# OS-MPS_Preamp_V1.net
KiCad netlist of a schematic drawn in EAGLE
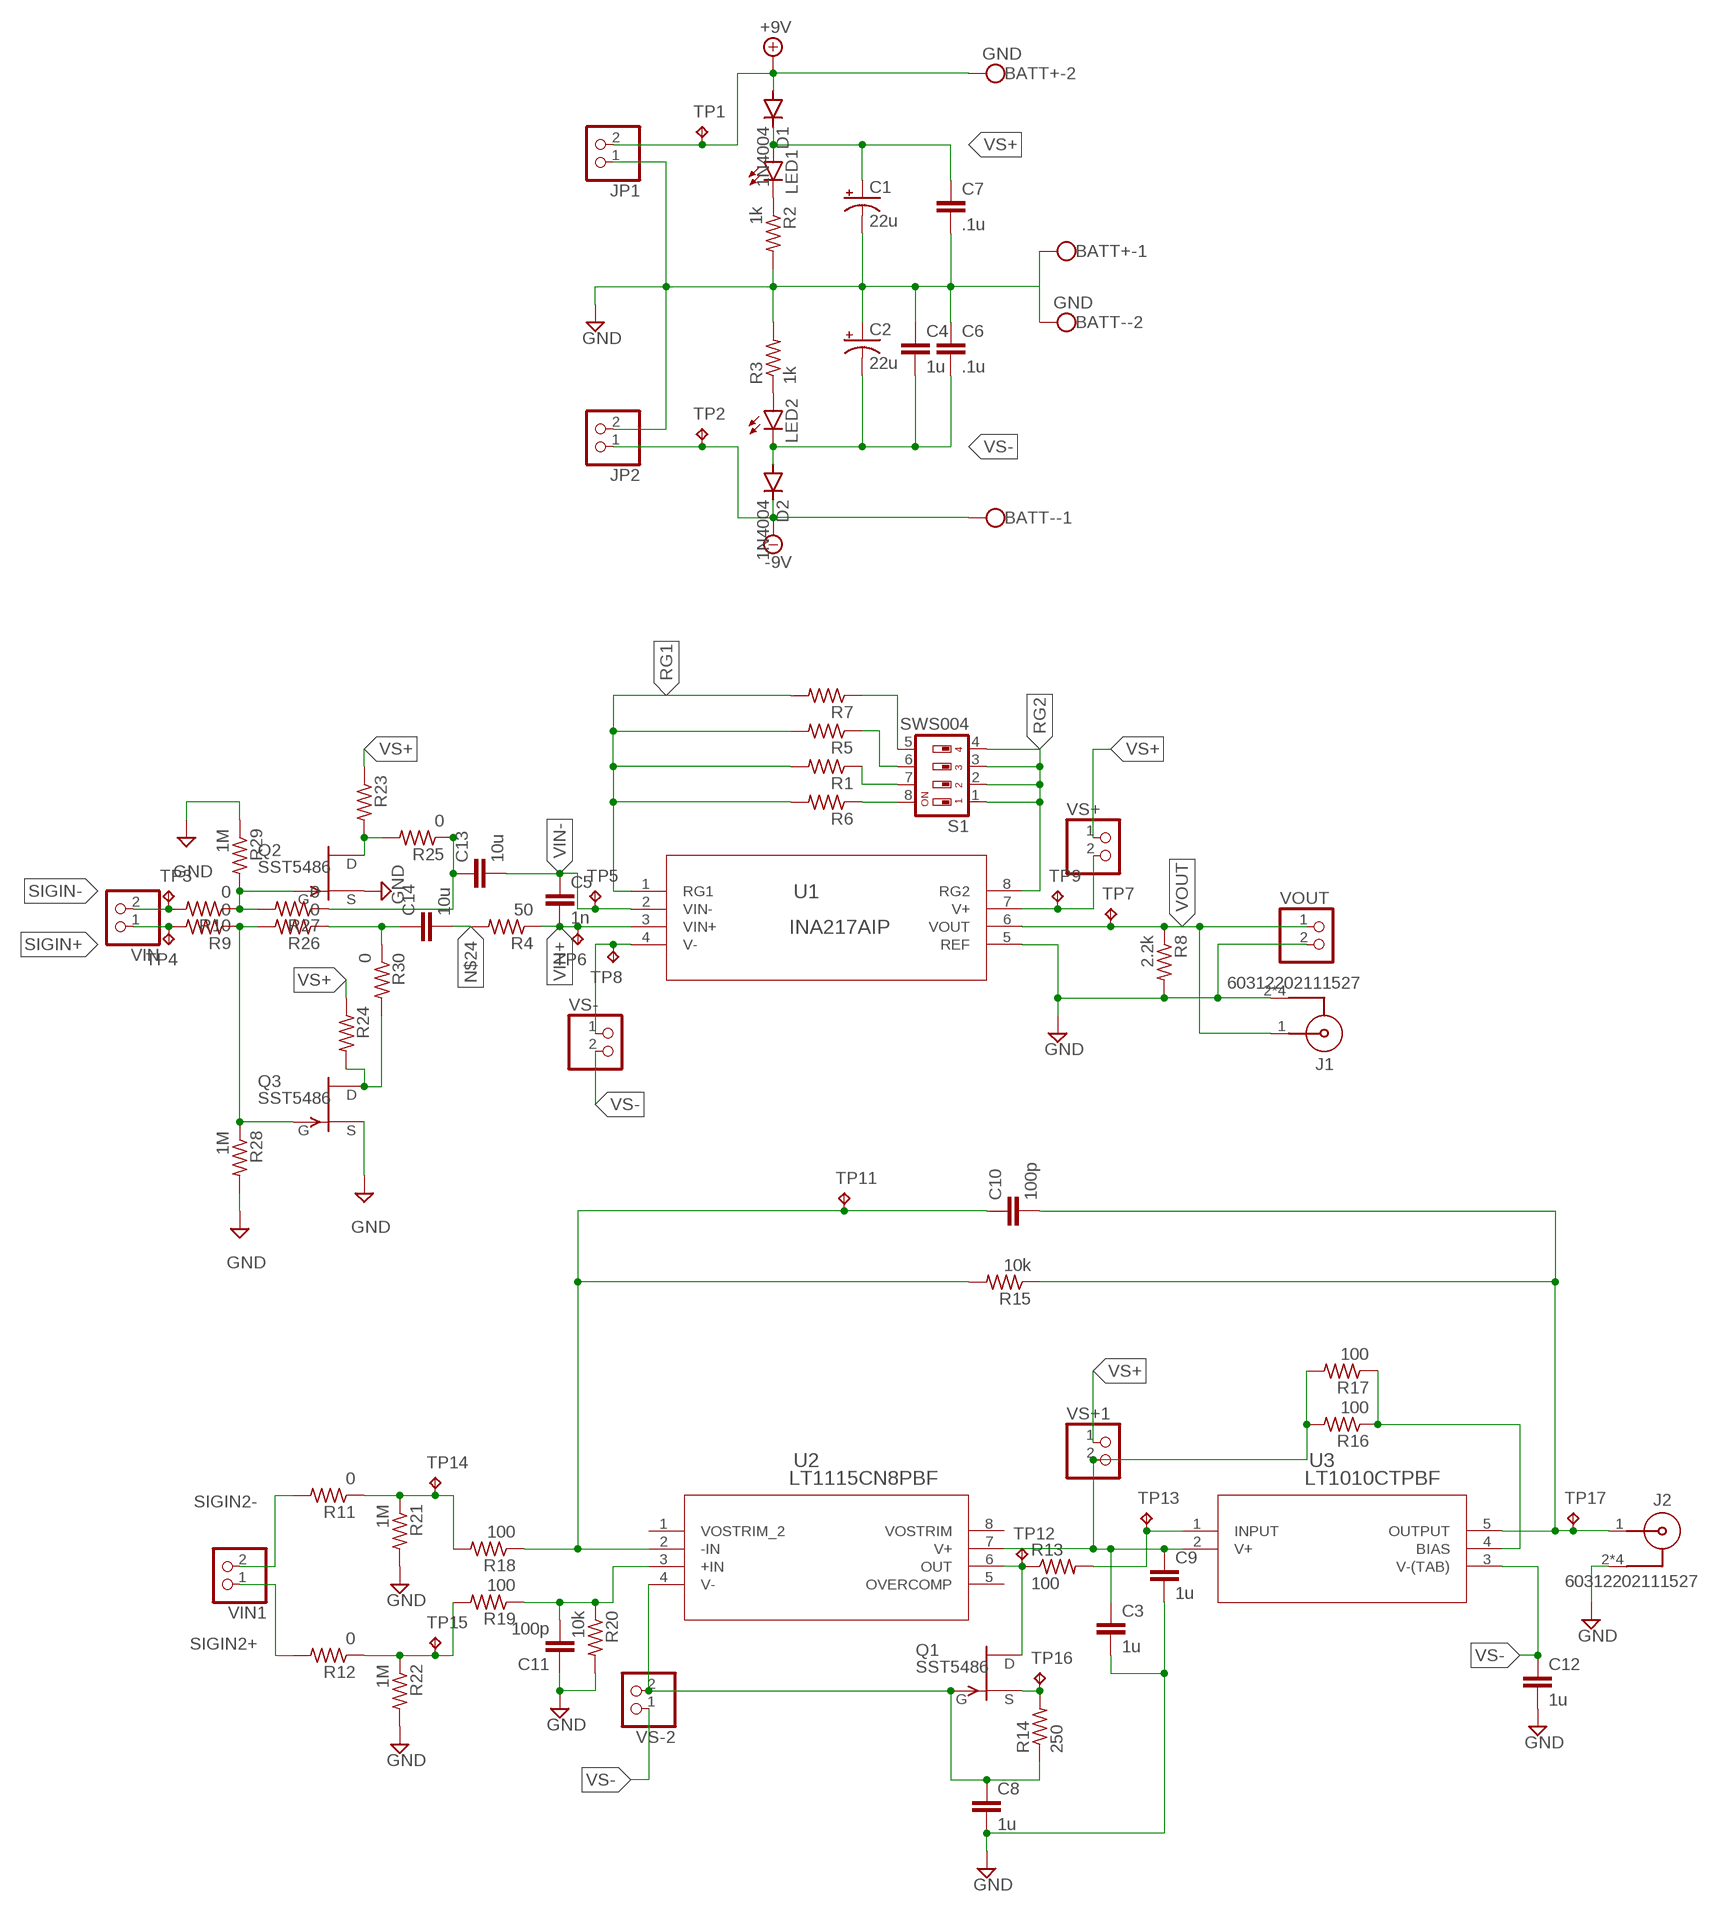
[diagram p0: schematic, sheet 1]

(export (version "E")
  (design (tool "Eeschema 10.0.6"))
  (components
    (comp (ref "BATT+")
      (value "GND")
      (footprint "eagle-import:W237-102")
      (fields (field (name "MPN") "237-102"))
      (libsource (lib "eagle-import") (part "W237-102"))
    )
    (comp (ref "BATT-")
      (value "GND")
      (footprint "eagle-import:W237-102")
      (fields (field (name "MPN") "237-102"))
      (libsource (lib "eagle-import") (part "W237-102"))
    )
    (comp (ref "C1")
      (value "22u")
      (footprint "eagle-import:TT2D6")
      (libsource (lib "eagle-import") (part "CPOL-USTT2D6"))
    )
    (comp (ref "C2")
      (value "22u")
      (footprint "eagle-import:TT2D6")
      (libsource (lib "eagle-import") (part "CPOL-USTT2D6"))
    )
    (comp (ref "C3")
      (value "1u")
      (footprint "eagle-import:C1206")
      (libsource (lib "eagle-import") (part "C-EUC1206"))
    )
    (comp (ref "C4")
      (value "1u")
      (footprint "eagle-import:C1206")
      (libsource (lib "eagle-import") (part "C-EUC1206"))
    )
    (comp (ref "C5")
      (value "1n")
      (footprint "eagle-import:C1206")
      (libsource (lib "eagle-import") (part "C-EUC1206"))
    )
    (comp (ref "C6")
      (value ".1u")
      (footprint "eagle-import:C1206")
      (libsource (lib "eagle-import") (part "C-EUC1206"))
    )
    (comp (ref "C7")
      (value ".1u")
      (footprint "eagle-import:C1206")
      (libsource (lib "eagle-import") (part "C-EUC1206"))
    )
    (comp (ref "C8")
      (value "1u")
      (footprint "eagle-import:C1206")
      (libsource (lib "eagle-import") (part "C-EUC1206"))
    )
    (comp (ref "C9")
      (value "1u")
      (footprint "eagle-import:C1206")
      (libsource (lib "eagle-import") (part "C-EUC1206"))
    )
    (comp (ref "C10")
      (value "100p")
      (footprint "eagle-import:C1206")
      (libsource (lib "eagle-import") (part "C-EUC1206"))
    )
    (comp (ref "C11")
      (value "100p")
      (footprint "eagle-import:C1206")
      (libsource (lib "eagle-import") (part "C-EUC1206"))
    )
    (comp (ref "C12")
      (value "1u")
      (footprint "eagle-import:C1206")
      (libsource (lib "eagle-import") (part "C-EUC1206"))
    )
    (comp (ref "C13")
      (value "10u")
      (footprint "eagle-import:C1206")
      (libsource (lib "eagle-import") (part "C-EUC1206"))
    )
    (comp (ref "C14")
      (value "10u")
      (footprint "eagle-import:C1206")
      (libsource (lib "eagle-import") (part "C-EUC1206"))
    )
    (comp (ref "D1")
      (value "1N4004")
      (footprint "eagle-import:DO41-10")
      (libsource (lib "eagle-import") (part "1N4004"))
    )
    (comp (ref "D2")
      (value "1N4004")
      (footprint "eagle-import:DO41-10")
      (libsource (lib "eagle-import") (part "1N4004"))
    )
    (comp (ref "J1")
      (value "60312202111527")
      (footprint "eagle-import:60312202111527")
      (libsource (lib "eagle-import") (part "60312202111527"))
    )
    (comp (ref "J2")
      (value "60312202111527")
      (footprint "eagle-import:60312202111527")
      (libsource (lib "eagle-import") (part "60312202111527"))
    )
    (comp (ref "JP1")
      (value "PINHD-1X2")
      (footprint "eagle-import:1X02")
      (libsource (lib "eagle-import") (part "PINHD-1X2"))
    )
    (comp (ref "JP2")
      (value "PINHD-1X2")
      (footprint "eagle-import:1X02")
      (libsource (lib "eagle-import") (part "PINHD-1X2"))
    )
    (comp (ref "LED1")
      (value "LEDSML0805")
      (footprint "eagle-import:SML0805")
      (libsource (lib "eagle-import") (part "LEDSML0805"))
    )
    (comp (ref "LED2")
      (value "LEDSML0805")
      (footprint "eagle-import:SML0805")
      (libsource (lib "eagle-import") (part "LEDSML0805"))
    )
    (comp (ref "Q1")
      (value "SST5486")
      (footprint "eagle-import:SOT23")
      (libsource (lib "eagle-import") (part "?548SST6"))
    )
    (comp (ref "Q2")
      (value "SST5486")
      (footprint "eagle-import:SOT23")
      (libsource (lib "eagle-import") (part "?548SST6"))
    )
    (comp (ref "Q3")
      (value "SST5486")
      (footprint "eagle-import:SOT23")
      (libsource (lib "eagle-import") (part "?548SST6"))
    )
    (comp (ref "R1")
      (value "R-US_R0805")
      (footprint "eagle-import:R0805")
      (libsource (lib "eagle-import") (part "R-US_R0805"))
    )
    (comp (ref "R2")
      (value "1k")
      (footprint "eagle-import:R0805")
      (libsource (lib "eagle-import") (part "R-US_R0805"))
    )
    (comp (ref "R3")
      (value "1k")
      (footprint "eagle-import:R0805")
      (libsource (lib "eagle-import") (part "R-US_R0805"))
    )
    (comp (ref "R4")
      (value "50")
      (footprint "eagle-import:R0805")
      (libsource (lib "eagle-import") (part "R-US_R0805"))
    )
    (comp (ref "R5")
      (value "R-US_R0805")
      (footprint "eagle-import:R0805")
      (libsource (lib "eagle-import") (part "R-US_R0805"))
    )
    (comp (ref "R6")
      (value "R-US_R0805")
      (footprint "eagle-import:R0805")
      (libsource (lib "eagle-import") (part "R-US_R0805"))
    )
    (comp (ref "R7")
      (value "R-US_R0805")
      (footprint "eagle-import:R0805")
      (libsource (lib "eagle-import") (part "R-US_R0805"))
    )
    (comp (ref "R8")
      (value "2.2k")
      (footprint "eagle-import:R0805")
      (libsource (lib "eagle-import") (part "R-US_R0805"))
    )
    (comp (ref "R9")
      (value "0")
      (footprint "eagle-import:R0805")
      (libsource (lib "eagle-import") (part "R-US_R0805"))
    )
    (comp (ref "R10")
      (value "0")
      (footprint "eagle-import:R0805")
      (libsource (lib "eagle-import") (part "R-US_R0805"))
    )
    (comp (ref "R11")
      (value "0")
      (footprint "eagle-import:R0805")
      (libsource (lib "eagle-import") (part "R-US_R0805"))
    )
    (comp (ref "R12")
      (value "0")
      (footprint "eagle-import:R0805")
      (libsource (lib "eagle-import") (part "R-US_R0805"))
    )
    (comp (ref "R13")
      (value "100")
      (footprint "eagle-import:R0805")
      (libsource (lib "eagle-import") (part "R-US_R0805"))
    )
    (comp (ref "R14")
      (value "250")
      (footprint "eagle-import:R0805")
      (libsource (lib "eagle-import") (part "R-US_R0805"))
    )
    (comp (ref "R15")
      (value "10k")
      (footprint "eagle-import:R0805")
      (libsource (lib "eagle-import") (part "R-US_R0805"))
    )
    (comp (ref "R16")
      (value "100")
      (footprint "eagle-import:R0805")
      (libsource (lib "eagle-import") (part "R-US_R0805"))
    )
    (comp (ref "R17")
      (value "100")
      (footprint "eagle-import:R0805")
      (libsource (lib "eagle-import") (part "R-US_R0805"))
    )
    (comp (ref "R18")
      (value "100")
      (footprint "eagle-import:R0805")
      (libsource (lib "eagle-import") (part "R-US_R0805"))
    )
    (comp (ref "R19")
      (value "100")
      (footprint "eagle-import:R0805")
      (libsource (lib "eagle-import") (part "R-US_R0805"))
    )
    (comp (ref "R20")
      (value "10k")
      (footprint "eagle-import:R0805")
      (libsource (lib "eagle-import") (part "R-US_R0805"))
    )
    (comp (ref "R21")
      (value "1M")
      (footprint "eagle-import:R0805")
      (libsource (lib "eagle-import") (part "R-US_R0805"))
    )
    (comp (ref "R22")
      (value "1M")
      (footprint "eagle-import:R0805")
      (libsource (lib "eagle-import") (part "R-US_R0805"))
    )
    (comp (ref "R23")
      (value "R-US_R0805")
      (footprint "eagle-import:R0805")
      (libsource (lib "eagle-import") (part "R-US_R0805"))
    )
    (comp (ref "R24")
      (value "R-US_R0805")
      (footprint "eagle-import:R0805")
      (libsource (lib "eagle-import") (part "R-US_R0805"))
    )
    (comp (ref "R25")
      (value "0")
      (footprint "eagle-import:R0805")
      (libsource (lib "eagle-import") (part "R-US_R0805"))
    )
    (comp (ref "R26")
      (value "0")
      (footprint "eagle-import:R0805")
      (libsource (lib "eagle-import") (part "R-US_R0805"))
    )
    (comp (ref "R27")
      (value "0")
      (footprint "eagle-import:R0805")
      (libsource (lib "eagle-import") (part "R-US_R0805"))
    )
    (comp (ref "R28")
      (value "1M")
      (footprint "eagle-import:R0805")
      (libsource (lib "eagle-import") (part "R-US_R0805"))
    )
    (comp (ref "R29")
      (value "1M")
      (footprint "eagle-import:R0805")
      (libsource (lib "eagle-import") (part "R-US_R0805"))
    )
    (comp (ref "R30")
      (value "0")
      (footprint "eagle-import:R0805")
      (libsource (lib "eagle-import") (part "R-US_R0805"))
    )
    (comp (ref "S1")
      (value "SWS004")
      (footprint "eagle-import:SMS-004")
      (libsource (lib "eagle-import") (part "SWS004"))
    )
    (comp (ref "TP1")
      (value "TPB2,54")
      (footprint "eagle-import:B2,54")
      (libsource (lib "eagle-import") (part "TPB2,54"))
    )
    (comp (ref "TP2")
      (value "TPB2,54")
      (footprint "eagle-import:B2,54")
      (libsource (lib "eagle-import") (part "TPB2,54"))
    )
    (comp (ref "TP3")
      (value "TPTP20SQ")
      (footprint "eagle-import:TP20SQ")
      (libsource (lib "eagle-import") (part "TPTP20SQ"))
    )
    (comp (ref "TP4")
      (value "TPTP20SQ")
      (footprint "eagle-import:TP20SQ")
      (libsource (lib "eagle-import") (part "TPTP20SQ"))
    )
    (comp (ref "TP5")
      (value "TPTP20SQ")
      (footprint "eagle-import:TP20SQ")
      (libsource (lib "eagle-import") (part "TPTP20SQ"))
    )
    (comp (ref "TP6")
      (value "TPTP20SQ")
      (footprint "eagle-import:TP20SQ")
      (libsource (lib "eagle-import") (part "TPTP20SQ"))
    )
    (comp (ref "TP7")
      (value "TPTP20SQ")
      (footprint "eagle-import:TP20SQ")
      (libsource (lib "eagle-import") (part "TPTP20SQ"))
    )
    (comp (ref "TP8")
      (value "TPTP20SQ")
      (footprint "eagle-import:TP20SQ")
      (libsource (lib "eagle-import") (part "TPTP20SQ"))
    )
    (comp (ref "TP9")
      (value "TPTP20SQ")
      (footprint "eagle-import:TP20SQ")
      (libsource (lib "eagle-import") (part "TPTP20SQ"))
    )
    (comp (ref "TP11")
      (value "TPTP20SQ")
      (footprint "eagle-import:TP20SQ")
      (libsource (lib "eagle-import") (part "TPTP20SQ"))
    )
    (comp (ref "TP12")
      (value "TPTP20SQ")
      (footprint "eagle-import:TP20SQ")
      (libsource (lib "eagle-import") (part "TPTP20SQ"))
    )
    (comp (ref "TP13")
      (value "TPTP20SQ")
      (footprint "eagle-import:TP20SQ")
      (libsource (lib "eagle-import") (part "TPTP20SQ"))
    )
    (comp (ref "TP14")
      (value "TPTP20SQ")
      (footprint "eagle-import:TP20SQ")
      (libsource (lib "eagle-import") (part "TPTP20SQ"))
    )
    (comp (ref "TP15")
      (value "TPTP20SQ")
      (footprint "eagle-import:TP20SQ")
      (libsource (lib "eagle-import") (part "TPTP20SQ"))
    )
    (comp (ref "TP16")
      (value "TPTP20SQ")
      (footprint "eagle-import:TP20SQ")
      (libsource (lib "eagle-import") (part "TPTP20SQ"))
    )
    (comp (ref "TP17")
      (value "TPTP20SQ")
      (footprint "eagle-import:TP20SQ")
      (libsource (lib "eagle-import") (part "TPTP20SQ"))
    )
    (comp (ref "U1")
      (value "INA217AIP")
      (footprint "eagle-import:P8")
      (fields (field (name "GENERIC_PART_NUMBER") "INA217") (field (name "MANUFACTURER") "Texas Instruments"))
      (libsource (lib "eagle-import") (part "INA217AIP"))
    )
    (comp (ref "U2")
      (value "LT1115CN8PBF")
      (footprint "eagle-import:PDIP-8_N_LIT")
      (fields (field (name "MANUFACTURER_PART_NUMBER") "LT1115CN8#PBF"))
      (libsource (lib "eagle-import") (part "LT1115CN8PBF"))
    )
    (comp (ref "U3")
      (value "LT1010CTPBF")
      (footprint "eagle-import:TO220-5_T")
      (fields (field (name "MANUFACTURER_PART_NUMBER") "LT1010CT#PBF"))
      (libsource (lib "eagle-import") (part "LT1010CTPBF"))
    )
    (comp (ref "VIN")
      (value "PINHD-1X2")
      (footprint "eagle-import:1X02")
      (libsource (lib "eagle-import") (part "PINHD-1X2"))
    )
    (comp (ref "VIN1")
      (value "PINHD-1X2")
      (footprint "eagle-import:1X02")
      (libsource (lib "eagle-import") (part "PINHD-1X2"))
    )
    (comp (ref "VOUT")
      (value "PINHD-1X2")
      (footprint "eagle-import:1X02")
      (libsource (lib "eagle-import") (part "PINHD-1X2"))
    )
    (comp (ref "VS+")
      (value "PINHD-1X2")
      (footprint "eagle-import:1X02")
      (libsource (lib "eagle-import") (part "PINHD-1X2"))
    )
    (comp (ref "VS+1")
      (value "PINHD-1X2")
      (footprint "eagle-import:1X02")
      (libsource (lib "eagle-import") (part "PINHD-1X2"))
    )
    (comp (ref "VS-")
      (value "PINHD-1X2")
      (footprint "eagle-import:1X02")
      (libsource (lib "eagle-import") (part "PINHD-1X2"))
    )
    (comp (ref "VS-2")
      (value "PINHD-1X2")
      (footprint "eagle-import:1X02")
      (libsource (lib "eagle-import") (part "PINHD-1X2"))
    )
  )
  (nets
    (net (code "1") (name "+9V") (class "Default")
      (node (ref "BATT+") (pin "2") (pinfunction "KL_2") (pintype "passive"))
      (node (ref "D1") (pin "A") (pinfunction "A_A") (pintype "passive"))
      (node (ref "JP1") (pin "2") (pinfunction "2_2") (pintype "passive"))
      (node (ref "TP1") (pin "TP") (pinfunction "TP_TP") (pintype "input"))
    )
    (net (code "2") (name "-9V") (class "Default")
      (node (ref "BATT-") (pin "1") (pinfunction "KL_1") (pintype "passive"))
      (node (ref "D2") (pin "C") (pinfunction "C_C") (pintype "passive"))
      (node (ref "JP2") (pin "1") (pinfunction "1_1") (pintype "passive"))
      (node (ref "TP2") (pin "TP") (pinfunction "TP_TP") (pintype "input"))
    )
    (net (code "3") (name "/SIGIN2+") (class "Default")
      (node (ref "R12") (pin "2") (pinfunction "2_2") (pintype "passive"))
      (node (ref "VIN1") (pin "1") (pinfunction "1_1") (pintype "passive"))
    )
    (net (code "4") (name "/SIGIN2-") (class "Default")
      (node (ref "R11") (pin "2") (pinfunction "2_2") (pintype "passive"))
      (node (ref "VIN1") (pin "2") (pinfunction "2_2") (pintype "passive"))
    )
    (net (code "5") (name "GND") (class "Default")
      (node (ref "BATT+") (pin "1") (pinfunction "KL_1") (pintype "passive"))
      (node (ref "BATT-") (pin "2") (pinfunction "KL_2") (pintype "passive"))
      (node (ref "C1") (pin "-") (pinfunction "-_-") (pintype "passive"))
      (node (ref "C11") (pin "1") (pinfunction "1_1") (pintype "passive"))
      (node (ref "C12") (pin "2") (pinfunction "2_2") (pintype "passive"))
      (node (ref "C2") (pin "+") (pinfunction "+_+") (pintype "passive"))
      (node (ref "C3") (pin "2") (pinfunction "2_2") (pintype "passive"))
      (node (ref "C4") (pin "1") (pinfunction "1_1") (pintype "passive"))
      (node (ref "C6") (pin "1") (pinfunction "1_1") (pintype "passive"))
      (node (ref "C7") (pin "2") (pinfunction "2_2") (pintype "passive"))
      (node (ref "C8") (pin "2") (pinfunction "2_2") (pintype "passive"))
      (node (ref "C9") (pin "2") (pinfunction "2_2") (pintype "passive"))
      (node (ref "J1") (pin "2") (pinfunction "2_2") (pintype "passive"))
      (node (ref "J1") (pin "3") (pinfunction "2_3") (pintype "passive"))
      (node (ref "J1") (pin "4") (pinfunction "2_4") (pintype "passive"))
      (node (ref "J1") (pin "5") (pinfunction "2_5") (pintype "passive"))
      (node (ref "J2") (pin "2") (pinfunction "2_2") (pintype "passive"))
      (node (ref "J2") (pin "3") (pinfunction "2_3") (pintype "passive"))
      (node (ref "J2") (pin "4") (pinfunction "2_4") (pintype "passive"))
      (node (ref "J2") (pin "5") (pinfunction "2_5") (pintype "passive"))
      (node (ref "JP1") (pin "1") (pinfunction "1_1") (pintype "passive"))
      (node (ref "JP2") (pin "2") (pinfunction "2_2") (pintype "passive"))
      (node (ref "Q2") (pin "2") (pinfunction "S_2") (pintype "passive"))
      (node (ref "Q3") (pin "2") (pinfunction "S_2") (pintype "passive"))
      (node (ref "R2") (pin "2") (pinfunction "2_2") (pintype "passive"))
      (node (ref "R20") (pin "2") (pinfunction "2_2") (pintype "passive"))
      (node (ref "R21") (pin "2") (pinfunction "2_2") (pintype "passive"))
      (node (ref "R22") (pin "2") (pinfunction "2_2") (pintype "passive"))
      (node (ref "R28") (pin "2") (pinfunction "2_2") (pintype "passive"))
      (node (ref "R29") (pin "1") (pinfunction "1_1") (pintype "passive"))
      (node (ref "R3") (pin "2") (pinfunction "2_2") (pintype "passive"))
      (node (ref "R8") (pin "2") (pinfunction "2_2") (pintype "passive"))
      (node (ref "U1") (pin "5") (pinfunction "REF_5") (pintype "passive"))
      (node (ref "VOUT") (pin "2") (pinfunction "2_2") (pintype "passive"))
    )
    (net (code "6") (name "N$24") (class "Default")
      (node (ref "C14") (pin "2") (pinfunction "2_2") (pintype "passive"))
      (node (ref "R4") (pin "2") (pinfunction "2_2") (pintype "passive"))
    )
    (net (code "7") (name "Net-(C13-Pad1)") (class "Default")
      (node (ref "C13") (pin "1") (pinfunction "1_1") (pintype "passive"))
      (node (ref "R25") (pin "1") (pinfunction "1_1") (pintype "passive"))
      (node (ref "R27") (pin "1") (pinfunction "1_1") (pintype "passive"))
    )
    (net (code "8") (name "Net-(C14-Pad1)") (class "Default")
      (node (ref "C14") (pin "1") (pinfunction "1_1") (pintype "passive"))
      (node (ref "R26") (pin "1") (pinfunction "1_1") (pintype "passive"))
      (node (ref "R30") (pin "1") (pinfunction "1_1") (pintype "passive"))
    )
    (net (code "9") (name "Net-(LED1-PadC)") (class "Default")
      (node (ref "LED1") (pin "C") (pinfunction "C_C") (pintype "passive"))
      (node (ref "R2") (pin "1") (pinfunction "1_1") (pintype "passive"))
    )
    (net (code "10") (name "Net-(LED2-PadA)") (class "Default")
      (node (ref "LED2") (pin "A") (pinfunction "A_A") (pintype "passive"))
      (node (ref "R3") (pin "1") (pinfunction "1_1") (pintype "passive"))
    )
    (net (code "11") (name "Net-(Q1-D)") (class "Default")
      (node (ref "Q1") (pin "1") (pinfunction "D_1") (pintype "passive"))
      (node (ref "R13") (pin "1") (pinfunction "1_1") (pintype "passive"))
      (node (ref "TP12") (pin "TP") (pinfunction "TP_TP") (pintype "input"))
      (node (ref "U2") (pin "6") (pinfunction "OUT_6") (pintype "output"))
    )
    (net (code "12") (name "Net-(Q1-G)") (class "Default")
      (node (ref "C8") (pin "1") (pinfunction "1_1") (pintype "passive"))
      (node (ref "Q1") (pin "3") (pinfunction "G_3") (pintype "passive"))
      (node (ref "R14") (pin "1") (pinfunction "1_1") (pintype "passive"))
      (node (ref "U2") (pin "4") (pinfunction "V-_4") (pintype "power_in"))
      (node (ref "VS-2") (pin "2") (pinfunction "2_2") (pintype "passive"))
    )
    (net (code "13") (name "Net-(Q1-S)") (class "Default")
      (node (ref "Q1") (pin "2") (pinfunction "S_2") (pintype "passive"))
      (node (ref "R14") (pin "2") (pinfunction "2_2") (pintype "passive"))
      (node (ref "TP16") (pin "TP") (pinfunction "TP_TP") (pintype "input"))
    )
    (net (code "14") (name "Net-(Q2-D)") (class "Default")
      (node (ref "Q2") (pin "1") (pinfunction "D_1") (pintype "passive"))
      (node (ref "R23") (pin "2") (pinfunction "2_2") (pintype "passive"))
      (node (ref "R25") (pin "2") (pinfunction "2_2") (pintype "passive"))
    )
    (net (code "15") (name "Net-(Q2-G)") (class "Default")
      (node (ref "Q2") (pin "3") (pinfunction "G_3") (pintype "passive"))
      (node (ref "R10") (pin "1") (pinfunction "1_1") (pintype "passive"))
      (node (ref "R27") (pin "2") (pinfunction "2_2") (pintype "passive"))
      (node (ref "R29") (pin "2") (pinfunction "2_2") (pintype "passive"))
    )
    (net (code "16") (name "Net-(Q3-D)") (class "Default")
      (node (ref "Q3") (pin "1") (pinfunction "D_1") (pintype "passive"))
      (node (ref "R24") (pin "2") (pinfunction "2_2") (pintype "passive"))
      (node (ref "R30") (pin "2") (pinfunction "2_2") (pintype "passive"))
    )
    (net (code "17") (name "Net-(Q3-G)") (class "Default")
      (node (ref "Q3") (pin "3") (pinfunction "G_3") (pintype "passive"))
      (node (ref "R26") (pin "2") (pinfunction "2_2") (pintype "passive"))
      (node (ref "R28") (pin "1") (pinfunction "1_1") (pintype "passive"))
      (node (ref "R9") (pin "1") (pinfunction "1_1") (pintype "passive"))
    )
    (net (code "18") (name "Net-(R1-Pad1)") (class "Default")
      (node (ref "R1") (pin "1") (pinfunction "1_1") (pintype "passive"))
      (node (ref "S1") (pin "7") (pinfunction "7_7") (pintype "passive"))
    )
    (net (code "19") (name "Net-(R5-Pad1)") (class "Default")
      (node (ref "R5") (pin "1") (pinfunction "1_1") (pintype "passive"))
      (node (ref "S1") (pin "6") (pinfunction "6_6") (pintype "passive"))
    )
    (net (code "20") (name "Net-(R6-Pad1)") (class "Default")
      (node (ref "R6") (pin "1") (pinfunction "1_1") (pintype "passive"))
      (node (ref "S1") (pin "8") (pinfunction "8_8") (pintype "passive"))
    )
    (net (code "21") (name "Net-(R7-Pad1)") (class "Default")
      (node (ref "R7") (pin "1") (pinfunction "1_1") (pintype "passive"))
      (node (ref "S1") (pin "5") (pinfunction "5_5") (pintype "passive"))
    )
    (net (code "22") (name "Net-(R11-Pad1)") (class "Default")
      (node (ref "R11") (pin "1") (pinfunction "1_1") (pintype "passive"))
      (node (ref "R18") (pin "2") (pinfunction "2_2") (pintype "passive"))
      (node (ref "R21") (pin "1") (pinfunction "1_1") (pintype "passive"))
      (node (ref "TP14") (pin "TP") (pinfunction "TP_TP") (pintype "input"))
    )
    (net (code "23") (name "Net-(R12-Pad1)") (class "Default")
      (node (ref "R12") (pin "1") (pinfunction "1_1") (pintype "passive"))
      (node (ref "R19") (pin "2") (pinfunction "2_2") (pintype "passive"))
      (node (ref "R22") (pin "1") (pinfunction "1_1") (pintype "passive"))
      (node (ref "TP15") (pin "TP") (pinfunction "TP_TP") (pintype "input"))
    )
    (net (code "24") (name "Net-(U1-V+)") (class "Default")
      (node (ref "TP9") (pin "TP") (pinfunction "TP_TP") (pintype "input"))
      (node (ref "U1") (pin "7") (pinfunction "V+_7") (pintype "power_in"))
      (node (ref "VS+") (pin "2") (pinfunction "2_2") (pintype "passive"))
    )
    (net (code "25") (name "Net-(U1-V-)") (class "Default")
      (node (ref "TP8") (pin "TP") (pinfunction "TP_TP") (pintype "input"))
      (node (ref "U1") (pin "4") (pinfunction "V-_4") (pintype "power_in"))
      (node (ref "VS-") (pin "1") (pinfunction "1_1") (pintype "passive"))
    )
    (net (code "26") (name "Net-(U2-+IN)") (class "Default")
      (node (ref "C11") (pin "2") (pinfunction "2_2") (pintype "passive"))
      (node (ref "R19") (pin "1") (pinfunction "1_1") (pintype "passive"))
      (node (ref "R20") (pin "1") (pinfunction "1_1") (pintype "passive"))
      (node (ref "U2") (pin "3") (pinfunction "+IN_3") (pintype "input"))
    )
    (net (code "27") (name "Net-(U2--IN)") (class "Default")
      (node (ref "C10") (pin "1") (pinfunction "1_1") (pintype "passive"))
      (node (ref "R15") (pin "2") (pinfunction "2_2") (pintype "passive"))
      (node (ref "R18") (pin "1") (pinfunction "1_1") (pintype "passive"))
      (node (ref "TP11") (pin "TP") (pinfunction "TP_TP") (pintype "input"))
      (node (ref "U2") (pin "2") (pinfunction "-IN_2") (pintype "input"))
    )
    (net (code "28") (name "Net-(U2-V+)") (class "Default")
      (node (ref "C3") (pin "1") (pinfunction "1_1") (pintype "passive"))
      (node (ref "C9") (pin "1") (pinfunction "1_1") (pintype "passive"))
      (node (ref "R16") (pin "2") (pinfunction "2_2") (pintype "passive"))
      (node (ref "R17") (pin "2") (pinfunction "2_2") (pintype "passive"))
      (node (ref "U2") (pin "7") (pinfunction "V+_7") (pintype "power_in"))
      (node (ref "U3") (pin "2") (pinfunction "V+_2") (pintype "power_in"))
      (node (ref "VS+1") (pin "2") (pinfunction "2_2") (pintype "passive"))
    )
    (net (code "29") (name "Net-(U3-BIAS)") (class "Default")
      (node (ref "R16") (pin "1") (pinfunction "1_1") (pintype "passive"))
      (node (ref "R17") (pin "1") (pinfunction "1_1") (pintype "passive"))
      (node (ref "U3") (pin "4") (pinfunction "BIAS_4") (pintype "passive"))
    )
    (net (code "30") (name "Net-(U3-INPUT)") (class "Default")
      (node (ref "R13") (pin "2") (pinfunction "2_2") (pintype "passive"))
      (node (ref "TP13") (pin "TP") (pinfunction "TP_TP") (pintype "input"))
      (node (ref "U3") (pin "1") (pinfunction "INPUT_1") (pintype "input"))
    )
    (net (code "31") (name "Net-(U3-OUTPUT)") (class "Default")
      (node (ref "C10") (pin "2") (pinfunction "2_2") (pintype "passive"))
      (node (ref "J2") (pin "1") (pinfunction "1_1") (pintype "passive"))
      (node (ref "R15") (pin "1") (pinfunction "1_1") (pintype "passive"))
      (node (ref "TP17") (pin "TP") (pinfunction "TP_TP") (pintype "input"))
      (node (ref "U3") (pin "5") (pinfunction "OUTPUT_5") (pintype "output"))
    )
    (net (code "32") (name "RG1") (class "Default")
      (node (ref "R1") (pin "2") (pinfunction "2_2") (pintype "passive"))
      (node (ref "R5") (pin "2") (pinfunction "2_2") (pintype "passive"))
      (node (ref "R6") (pin "2") (pinfunction "2_2") (pintype "passive"))
      (node (ref "R7") (pin "2") (pinfunction "2_2") (pintype "passive"))
      (node (ref "U1") (pin "1") (pinfunction "RG1_1") (pintype "passive"))
    )
    (net (code "33") (name "RG2") (class "Default")
      (node (ref "S1") (pin "1") (pinfunction "1_1") (pintype "passive"))
      (node (ref "S1") (pin "2") (pinfunction "2_2") (pintype "passive"))
      (node (ref "S1") (pin "3") (pinfunction "3_3") (pintype "passive"))
      (node (ref "S1") (pin "4") (pinfunction "4_4") (pintype "passive"))
      (node (ref "U1") (pin "8") (pinfunction "RG2_8") (pintype "passive"))
    )
    (net (code "34") (name "SIGIN+") (class "Default")
      (node (ref "R9") (pin "2") (pinfunction "2_2") (pintype "passive"))
      (node (ref "TP4") (pin "TP") (pinfunction "TP_TP") (pintype "input"))
      (node (ref "VIN") (pin "1") (pinfunction "1_1") (pintype "passive"))
    )
    (net (code "35") (name "SIGIN-") (class "Default")
      (node (ref "R10") (pin "2") (pinfunction "2_2") (pintype "passive"))
      (node (ref "TP3") (pin "TP") (pinfunction "TP_TP") (pintype "input"))
      (node (ref "VIN") (pin "2") (pinfunction "2_2") (pintype "passive"))
    )
    (net (code "36") (name "VIN+") (class "Default")
      (node (ref "C5") (pin "2") (pinfunction "2_2") (pintype "passive"))
      (node (ref "R4") (pin "1") (pinfunction "1_1") (pintype "passive"))
      (node (ref "TP6") (pin "TP") (pinfunction "TP_TP") (pintype "input"))
      (node (ref "U1") (pin "3") (pinfunction "VIN+_3") (pintype "passive"))
    )
    (net (code "37") (name "VIN-") (class "Default")
      (node (ref "C13") (pin "2") (pinfunction "2_2") (pintype "passive"))
      (node (ref "C5") (pin "1") (pinfunction "1_1") (pintype "passive"))
      (node (ref "TP5") (pin "TP") (pinfunction "TP_TP") (pintype "input"))
      (node (ref "U1") (pin "2") (pinfunction "VIN-_2") (pintype "passive"))
    )
    (net (code "38") (name "VOUT") (class "Default")
      (node (ref "J1") (pin "1") (pinfunction "1_1") (pintype "passive"))
      (node (ref "R8") (pin "1") (pinfunction "1_1") (pintype "passive"))
      (node (ref "TP7") (pin "TP") (pinfunction "TP_TP") (pintype "input"))
      (node (ref "U1") (pin "6") (pinfunction "VOUT_6") (pintype "output"))
      (node (ref "VOUT") (pin "1") (pinfunction "1_1") (pintype "passive"))
    )
    (net (code "39") (name "VS+") (class "Default")
      (node (ref "C1") (pin "+") (pinfunction "+_+") (pintype "passive"))
      (node (ref "C7") (pin "1") (pinfunction "1_1") (pintype "passive"))
      (node (ref "D1") (pin "C") (pinfunction "C_C") (pintype "passive"))
      (node (ref "LED1") (pin "A") (pinfunction "A_A") (pintype "passive"))
      (node (ref "R23") (pin "1") (pinfunction "1_1") (pintype "passive"))
      (node (ref "R24") (pin "1") (pinfunction "1_1") (pintype "passive"))
      (node (ref "VS+") (pin "1") (pinfunction "1_1") (pintype "passive"))
      (node (ref "VS+1") (pin "1") (pinfunction "1_1") (pintype "passive"))
    )
    (net (code "40") (name "VS-") (class "Default")
      (node (ref "C12") (pin "1") (pinfunction "1_1") (pintype "passive"))
      (node (ref "C2") (pin "-") (pinfunction "-_-") (pintype "passive"))
      (node (ref "C4") (pin "2") (pinfunction "2_2") (pintype "passive"))
      (node (ref "C6") (pin "2") (pinfunction "2_2") (pintype "passive"))
      (node (ref "D2") (pin "A") (pinfunction "A_A") (pintype "passive"))
      (node (ref "LED2") (pin "C") (pinfunction "C_C") (pintype "passive"))
      (node (ref "U3") (pin "3") (pinfunction "V-(TAB)_3") (pintype "power_in"))
      (node (ref "VS-") (pin "2") (pinfunction "2_2") (pintype "passive"))
      (node (ref "VS-2") (pin "1") (pinfunction "1_1") (pintype "passive"))
    )
    (net (code "41") (name "unconnected-(U2-OVERCOMP-Pad5)") (class "Default")
      (node (ref "U2") (pin "5") (pinfunction "OVERCOMP_5") (pintype "passive"))
    )
    (net (code "42") (name "unconnected-(U2-VOSTRIM-Pad8)") (class "Default")
      (node (ref "U2") (pin "8") (pinfunction "VOSTRIM_8") (pintype "passive"))
    )
    (net (code "43") (name "unconnected-(U2-VOSTRIM_2-Pad1)") (class "Default")
      (node (ref "U2") (pin "1") (pinfunction "VOSTRIM_2_1") (pintype "passive"))
    )
  )
)
